# AVR_USB_Downloader_V2.net
KiCad netlist of a schematic drawn in Altium Designer
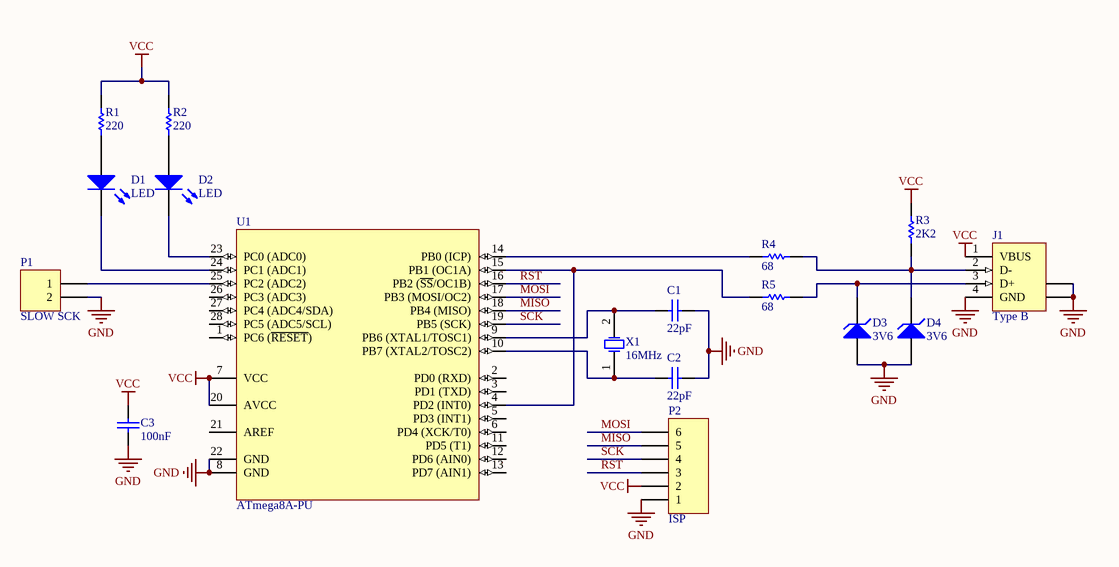
[diagram p0: AVR USB Downloader V2.SchDoc]

(export (version "E")
  (design (tool "Eeschema 10.0.6"))
  (components
    (comp (ref "C1")
      (value "22pF")
      (footprint "C025-024X044")
      (libsource (lib "toko-Embedded") (part "Capacitor"))
    )
    (comp (ref "C2")
      (value "22pF")
      (footprint "C025-024X044")
      (libsource (lib "toko-Embedded") (part "Capacitor"))
    )
    (comp (ref "C3")
      (value "100nF")
      (footprint "C025-024X044")
      (libsource (lib "toko-Embedded") (part "Capacitor"))
    )
    (comp (ref "D1") (value "LED") (footprint "LED3MM") (libsource (lib "toko-Embedded") (part "LED")))
    (comp (ref "D2") (value "LED") (footprint "LED3MM") (libsource (lib "toko-Embedded") (part "LED")))
    (comp (ref "D3") (value "3V6") (footprint "DO34Z7") (libsource (lib "toko-Embedded") (part "Zener")))
    (comp (ref "D4") (value "3V6") (footprint "DO34Z7") (libsource (lib "toko-Embedded") (part "Zener")))
    (comp (ref "J1")
      (value "Type B")
      (footprint "toko-Embedded:USB-A-H")
      (libsource (lib "toko-Embedded") (part "USB"))
    )
    (comp (ref "P1")
      (value "SLOW SCK")
      (footprint "HDR1X2")
      (description "Header, 2-Pin")
      (fields (field (name "PUBLISHER") "Altium Limited"))
      (libsource (lib "Miscellaneous Connectors") (part "Header 2"))
    )
    (comp (ref "P2")
      (value "ISP")
      (footprint "HDR1X6H")
      (description "Header, 6-Pin, Right Angle")
      (fields (field (name "PUBLISHER") "Altium Limited"))
      (libsource (lib "Miscellaneous Connectors") (part "Header 6H"))
    )
    (comp (ref "R1") (value "220") (footprint "0207/10") (libsource (lib "toko-Embedded") (part "Resistor")))
    (comp (ref "R2") (value "220") (footprint "0207/10") (libsource (lib "toko-Embedded") (part "Resistor")))
    (comp (ref "R3") (value "2K2") (footprint "0207/10") (libsource (lib "toko-Embedded") (part "Resistor")))
    (comp (ref "R4") (value "68") (footprint "0207/10") (libsource (lib "toko-Embedded") (part "Resistor")))
    (comp (ref "R5") (value "68") (footprint "0207/10") (libsource (lib "toko-Embedded") (part "Resistor")))
    (comp (ref "U1")
      (value "ATmega8A-PU")
      (footprint "28P3")
      (fields (field (name "PUBLISHER") "Altium Limited"))
      (libsource (lib "Atmel Microcontroller 8-Bit megaAVR") (part "ATmega8A-PU"))
    )
    (comp (ref "X1") (value "16MHz") (footprint "HC49US") (libsource (lib "toko-Embedded") (part "Crystal")))
  )
  (nets
    (net (code "1") (name "/MISO") (class "Default")
      (node (ref "P2") (pin "5") (pinfunction "5_5") (pintype "passive"))
      (node (ref "U1") (pin "18") (pinfunction "PB4_(MISO)_18") (pintype "bidirectional"))
    )
    (net (code "2") (name "/MOSI") (class "Default")
      (node (ref "P2") (pin "6") (pinfunction "6_6") (pintype "passive"))
      (node (ref "U1") (pin "17") (pinfunction "PB3_(MOSI/OC2)_17") (pintype "bidirectional"))
    )
    (net (code "3") (name "/RST") (class "Default")
      (node (ref "P2") (pin "3") (pinfunction "3_3") (pintype "passive"))
      (node (ref "U1") (pin "16") (pinfunction "PB2_(~{SS}/OC1B)_16") (pintype "bidirectional"))
    )
    (net (code "4") (name "/SCK") (class "Default")
      (node (ref "P2") (pin "4") (pinfunction "4_4") (pintype "passive"))
      (node (ref "U1") (pin "19") (pinfunction "PB5_(SCK)_19") (pintype "bidirectional"))
    )
    (net (code "5") (name "GND") (class "Default")
      (node (ref "C1") (pin "1") (pinfunction "1_1") (pintype "passive"))
      (node (ref "C2") (pin "1") (pinfunction "1_1") (pintype "passive"))
      (node (ref "C3") (pin "1") (pinfunction "1_1") (pintype "passive"))
      (node (ref "D3") (pin "1") (pinfunction "A_1") (pintype "passive"))
      (node (ref "D4") (pin "1") (pinfunction "A_1") (pintype "passive"))
      (node (ref "J1") (pin "4") (pinfunction "GND_4") (pintype "power_in"))
      (node (ref "J1") (pin "5") (pinfunction "SHLD_5") (pintype "passive"))
      (node (ref "J1") (pin "6") (pinfunction "SHLD_6") (pintype "passive"))
      (node (ref "P1") (pin "2") (pinfunction "2_2") (pintype "passive"))
      (node (ref "P2") (pin "1") (pinfunction "1_1") (pintype "passive"))
      (node (ref "U1") (pin "22") (pinfunction "GND_22") (pintype "power_in"))
      (node (ref "U1") (pin "8") (pinfunction "GND_8") (pintype "power_in"))
    )
    (net (code "6") (name "Net-(D1-A)") (class "Default")
      (node (ref "D1") (pin "1") (pinfunction "A_1") (pintype "passive"))
      (node (ref "R1") (pin "1") (pinfunction "1_1") (pintype "passive"))
    )
    (net (code "7") (name "Net-(D1-K)") (class "Default")
      (node (ref "D1") (pin "2") (pinfunction "K_2") (pintype "passive"))
      (node (ref "U1") (pin "24") (pinfunction "PC1_(ADC1)_24") (pintype "bidirectional"))
    )
    (net (code "8") (name "Net-(D2-A)") (class "Default")
      (node (ref "D2") (pin "1") (pinfunction "A_1") (pintype "passive"))
      (node (ref "R2") (pin "1") (pinfunction "1_1") (pintype "passive"))
    )
    (net (code "9") (name "Net-(D2-K)") (class "Default")
      (node (ref "D2") (pin "2") (pinfunction "K_2") (pintype "passive"))
      (node (ref "U1") (pin "23") (pinfunction "PC0_(ADC0)_23") (pintype "bidirectional"))
    )
    (net (code "10") (name "Net-(D3-K)") (class "Default")
      (node (ref "D3") (pin "2") (pinfunction "K_2") (pintype "passive"))
      (node (ref "J1") (pin "3") (pinfunction "D+_3") (pintype "input"))
      (node (ref "R5") (pin "2") (pinfunction "2_2") (pintype "passive"))
    )
    (net (code "11") (name "Net-(D4-K)") (class "Default")
      (node (ref "D4") (pin "2") (pinfunction "K_2") (pintype "passive"))
      (node (ref "J1") (pin "2") (pinfunction "D-_2") (pintype "input"))
      (node (ref "R3") (pin "1") (pinfunction "1_1") (pintype "passive"))
      (node (ref "R4") (pin "2") (pinfunction "2_2") (pintype "passive"))
    )
    (net (code "12") (name "Net-(U1-PB0_(ICP))") (class "Default")
      (node (ref "R4") (pin "1") (pinfunction "1_1") (pintype "passive"))
      (node (ref "U1") (pin "14") (pinfunction "PB0_(ICP)_14") (pintype "bidirectional"))
    )
    (net (code "13") (name "Net-(U1-PB1_(OC1A))") (class "Default")
      (node (ref "R5") (pin "1") (pinfunction "1_1") (pintype "passive"))
      (node (ref "U1") (pin "15") (pinfunction "PB1_(OC1A)_15") (pintype "bidirectional"))
      (node (ref "U1") (pin "4") (pinfunction "PD2_(INT0)_4") (pintype "bidirectional"))
    )
    (net (code "14") (name "Net-(U1-PB6_(XTAL1{slash}TOSC1))") (class "Default")
      (node (ref "C1") (pin "2") (pinfunction "2_2") (pintype "passive"))
      (node (ref "U1") (pin "9") (pinfunction "PB6_(XTAL1/TOSC1)_9") (pintype "bidirectional"))
      (node (ref "X1") (pin "2") (pinfunction "OSC2_2") (pintype "passive"))
    )
    (net (code "15") (name "Net-(U1-PB7_(XTAL2{slash}TOSC2))") (class "Default")
      (node (ref "C2") (pin "2") (pinfunction "2_2") (pintype "passive"))
      (node (ref "U1") (pin "10") (pinfunction "PB7_(XTAL2/TOSC2)_10") (pintype "bidirectional"))
      (node (ref "X1") (pin "1") (pinfunction "OSC1_1") (pintype "passive"))
    )
    (net (code "16") (name "Net-(U1-PC2_(ADC2))") (class "Default")
      (node (ref "P1") (pin "1") (pinfunction "1_1") (pintype "passive"))
      (node (ref "U1") (pin "25") (pinfunction "PC2_(ADC2)_25") (pintype "bidirectional"))
    )
    (net (code "17") (name "VCC") (class "Default")
      (node (ref "C3") (pin "2") (pinfunction "2_2") (pintype "passive"))
      (node (ref "J1") (pin "1") (pinfunction "VBUS_1") (pintype "power_in"))
      (node (ref "P2") (pin "2") (pinfunction "2_2") (pintype "passive"))
      (node (ref "R1") (pin "2") (pinfunction "2_2") (pintype "passive"))
      (node (ref "R2") (pin "2") (pinfunction "2_2") (pintype "passive"))
      (node (ref "R3") (pin "2") (pinfunction "2_2") (pintype "passive"))
      (node (ref "U1") (pin "20") (pinfunction "AVCC_20") (pintype "power_in"))
      (node (ref "U1") (pin "7") (pinfunction "VCC_7") (pintype "power_in"))
    )
    (net (code "18") (name "unconnected-(U1-AREF-Pad21)") (class "Default")
      (node (ref "U1") (pin "21") (pinfunction "AREF_21") (pintype "passive"))
    )
    (net (code "19") (name "unconnected-(U1-PC3_(ADC3)-Pad26)") (class "Default")
      (node (ref "U1") (pin "26") (pinfunction "PC3_(ADC3)_26") (pintype "bidirectional"))
    )
    (net (code "20") (name "unconnected-(U1-PC4_(ADC4{slash}SDA)-Pad27)") (class "Default")
      (node (ref "U1") (pin "27") (pinfunction "PC4_(ADC4/SDA)_27") (pintype "bidirectional"))
    )
    (net (code "21") (name "unconnected-(U1-PC5_(ADC5{slash}SCL)-Pad28)") (class "Default")
      (node (ref "U1") (pin "28") (pinfunction "PC5_(ADC5/SCL)_28") (pintype "bidirectional"))
    )
    (net (code "22") (name "unconnected-(U1-PC6_(~{RESET})-Pad1)") (class "Default")
      (node (ref "U1") (pin "1") (pinfunction "PC6_(~{RESET})_1") (pintype "bidirectional"))
    )
    (net (code "23") (name "unconnected-(U1-PD0_(RXD)-Pad2)") (class "Default")
      (node (ref "U1") (pin "2") (pinfunction "PD0_(RXD)_2") (pintype "bidirectional"))
    )
    (net (code "24") (name "unconnected-(U1-PD1_(TXD)-Pad3)") (class "Default")
      (node (ref "U1") (pin "3") (pinfunction "PD1_(TXD)_3") (pintype "bidirectional"))
    )
    (net (code "25") (name "unconnected-(U1-PD3_(INT1)-Pad5)") (class "Default")
      (node (ref "U1") (pin "5") (pinfunction "PD3_(INT1)_5") (pintype "bidirectional"))
    )
    (net (code "26") (name "unconnected-(U1-PD4_(XCK{slash}T0)-Pad6)") (class "Default")
      (node (ref "U1") (pin "6") (pinfunction "PD4_(XCK/T0)_6") (pintype "bidirectional"))
    )
    (net (code "27") (name "unconnected-(U1-PD5_(T1)-Pad11)") (class "Default")
      (node (ref "U1") (pin "11") (pinfunction "PD5_(T1)_11") (pintype "bidirectional"))
    )
    (net (code "28") (name "unconnected-(U1-PD6_(AIN0)-Pad12)") (class "Default")
      (node (ref "U1") (pin "12") (pinfunction "PD6_(AIN0)_12") (pintype "bidirectional"))
    )
    (net (code "29") (name "unconnected-(U1-PD7_(AIN1)-Pad13)") (class "Default")
      (node (ref "U1") (pin "13") (pinfunction "PD7_(AIN1)_13") (pintype "bidirectional"))
    )
  )
)
